# edition_3-1.net
KiCad netlist of a schematic drawn in EAGLE
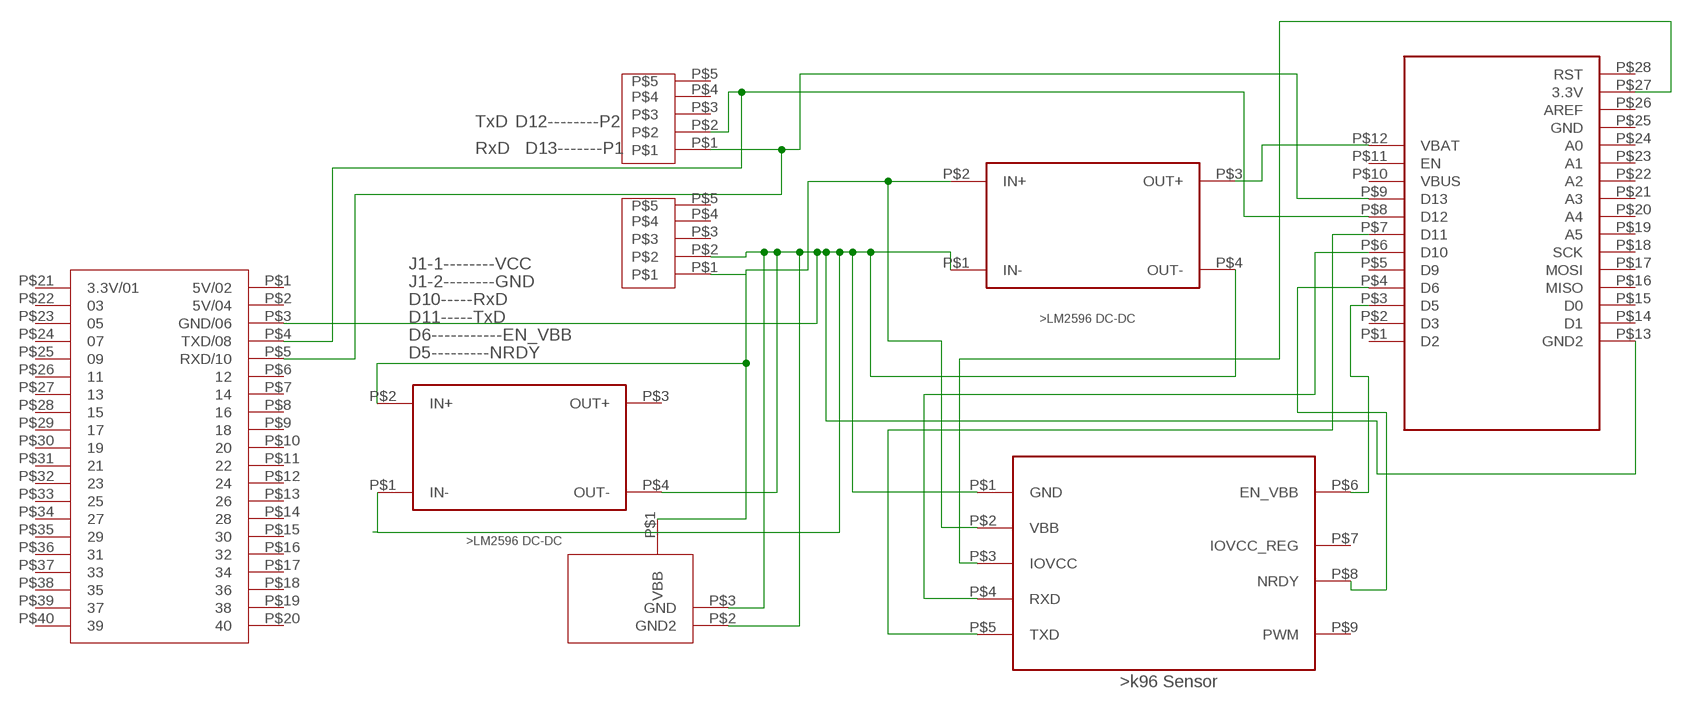
[diagram p0: schematic, sheet 1]

(export (version "E")
  (design (tool "Eeschema 10.0.6"))
  (components
    (comp (ref "DCDC1")
      (value "DCDC")
      (footprint "eagle-import:DCDC")
      (libsource (lib "eagle-import") (part "DCDC"))
    )
    (comp (ref "DCDC2")
      (value "DCDC")
      (footprint "eagle-import:DCDC")
      (libsource (lib "eagle-import") (part "DCDC"))
    )
    (comp (ref "FEATHER1")
      (value "FEATHER")
      (footprint "eagle-import:FEATHER")
      (libsource (lib "eagle-import") (part "FEATHER"))
    )
    (comp (ref "K96SENSOR1")
      (value "K96SENSOR")
      (footprint "eagle-import:K96SENSOR")
      (libsource (lib "eagle-import") (part "K96SENSOR"))
    )
    (comp (ref "PIN1")
      (value "PIN")
      (footprint "eagle-import:PIN")
      (libsource (lib "eagle-import") (part "PIN"))
    )
    (comp (ref "PIN2")
      (value "PIN")
      (footprint "eagle-import:PIN")
      (libsource (lib "eagle-import") (part "PIN"))
    )
    (comp (ref "U$1")
      (value "POWER")
      (footprint "eagle-import:POWERIN")
      (libsource (lib "eagle-import") (part "POWER"))
    )
    (comp (ref "U$2")
      (value "RASPBERRYPI")
      (footprint "eagle-import:RASPBERRYPI")
      (libsource (lib "eagle-import") (part "RASPBERRYPI"))
    )
  )
  (nets
    (net (code "1") (name "Net-(DCDC1-IN+)") (class "Default")
      (node (ref "DCDC1") (pin "P$2") (pinfunction "IN+_P$2") (pintype "bidirectional"))
      (node (ref "DCDC2") (pin "P$2") (pinfunction "IN+_P$2") (pintype "bidirectional"))
      (node (ref "K96SENSOR1") (pin "P$2") (pinfunction "VBB_P$2") (pintype "bidirectional"))
      (node (ref "PIN1") (pin "P$1") (pinfunction "P$1_P$1") (pintype "bidirectional"))
      (node (ref "U$1") (pin "P$1") (pinfunction "VBB_P$1") (pintype "bidirectional"))
    )
    (net (code "2") (name "Net-(DCDC1-IN-)") (class "Default")
      (node (ref "DCDC1") (pin "P$1") (pinfunction "IN-_P$1") (pintype "bidirectional"))
      (node (ref "DCDC1") (pin "P$4") (pinfunction "OUT-_P$4") (pintype "bidirectional"))
      (node (ref "DCDC2") (pin "P$1") (pinfunction "IN-_P$1") (pintype "bidirectional"))
      (node (ref "DCDC2") (pin "P$4") (pinfunction "OUT-_P$4") (pintype "bidirectional"))
      (node (ref "FEATHER1") (pin "P$13") (pinfunction "GND2_P$13") (pintype "bidirectional"))
      (node (ref "K96SENSOR1") (pin "P$1") (pinfunction "GND_P$1") (pintype "bidirectional"))
      (node (ref "PIN1") (pin "P$2") (pinfunction "P$2_P$2") (pintype "bidirectional"))
      (node (ref "U$1") (pin "P$2") (pinfunction "GND2_P$2") (pintype "bidirectional"))
      (node (ref "U$1") (pin "P$3") (pinfunction "GND_P$3") (pintype "bidirectional"))
      (node (ref "U$2") (pin "P$3") (pinfunction "GND/06_P$3") (pintype "bidirectional"))
    )
    (net (code "3") (name "Net-(DCDC1-OUT+)") (class "Default")
      (node (ref "DCDC1") (pin "P$3") (pinfunction "OUT+_P$3") (pintype "bidirectional"))
      (node (ref "FEATHER1") (pin "P$12") (pinfunction "VBAT_P$12") (pintype "bidirectional"))
    )
    (net (code "4") (name "Net-(FEATHER1-3.3V)") (class "Default")
      (node (ref "FEATHER1") (pin "P$27") (pinfunction "3.3V_P$27") (pintype "bidirectional"))
      (node (ref "K96SENSOR1") (pin "P$3") (pinfunction "IOVCC_P$3") (pintype "bidirectional"))
    )
    (net (code "5") (name "Net-(FEATHER1-D5)") (class "Default")
      (node (ref "FEATHER1") (pin "P$3") (pinfunction "D5_P$3") (pintype "bidirectional"))
      (node (ref "K96SENSOR1") (pin "P$6") (pinfunction "EN_VBB_P$6") (pintype "bidirectional"))
    )
    (net (code "6") (name "Net-(FEATHER1-D6)") (class "Default")
      (node (ref "FEATHER1") (pin "P$4") (pinfunction "D6_P$4") (pintype "bidirectional"))
      (node (ref "K96SENSOR1") (pin "P$8") (pinfunction "NRDY_P$8") (pintype "bidirectional"))
    )
    (net (code "7") (name "Net-(FEATHER1-D10)") (class "Default")
      (node (ref "FEATHER1") (pin "P$6") (pinfunction "D10_P$6") (pintype "bidirectional"))
      (node (ref "K96SENSOR1") (pin "P$4") (pinfunction "RXD_P$4") (pintype "bidirectional"))
    )
    (net (code "8") (name "Net-(FEATHER1-D11)") (class "Default")
      (node (ref "FEATHER1") (pin "P$7") (pinfunction "D11_P$7") (pintype "bidirectional"))
      (node (ref "K96SENSOR1") (pin "P$5") (pinfunction "TXD_P$5") (pintype "bidirectional"))
    )
    (net (code "9") (name "Net-(FEATHER1-D12)") (class "Default")
      (node (ref "FEATHER1") (pin "P$8") (pinfunction "D12_P$8") (pintype "bidirectional"))
      (node (ref "PIN2") (pin "P$2") (pinfunction "P$2_P$2") (pintype "bidirectional"))
      (node (ref "U$2") (pin "P$4") (pinfunction "TXD/08_P$4") (pintype "bidirectional"))
    )
    (net (code "10") (name "Net-(FEATHER1-D13)") (class "Default")
      (node (ref "FEATHER1") (pin "P$9") (pinfunction "D13_P$9") (pintype "bidirectional"))
      (node (ref "PIN2") (pin "P$1") (pinfunction "P$1_P$1") (pintype "bidirectional"))
      (node (ref "U$2") (pin "P$5") (pinfunction "RXD/10_P$5") (pintype "bidirectional"))
    )
    (net (code "11") (name "unconnected-(DCDC2-OUT+-PadP$3)") (class "Default")
      (node (ref "DCDC2") (pin "P$3") (pinfunction "OUT+_P$3") (pintype "bidirectional"))
    )
    (net (code "12") (name "unconnected-(FEATHER1-A0-PadP$24)") (class "Default")
      (node (ref "FEATHER1") (pin "P$24") (pinfunction "A0_P$24") (pintype "bidirectional"))
    )
    (net (code "13") (name "unconnected-(FEATHER1-A1-PadP$23)") (class "Default")
      (node (ref "FEATHER1") (pin "P$23") (pinfunction "A1_P$23") (pintype "bidirectional"))
    )
    (net (code "14") (name "unconnected-(FEATHER1-A2-PadP$22)") (class "Default")
      (node (ref "FEATHER1") (pin "P$22") (pinfunction "A2_P$22") (pintype "bidirectional"))
    )
    (net (code "15") (name "unconnected-(FEATHER1-A3-PadP$21)") (class "Default")
      (node (ref "FEATHER1") (pin "P$21") (pinfunction "A3_P$21") (pintype "bidirectional"))
    )
    (net (code "16") (name "unconnected-(FEATHER1-A4-PadP$20)") (class "Default")
      (node (ref "FEATHER1") (pin "P$20") (pinfunction "A4_P$20") (pintype "bidirectional"))
    )
    (net (code "17") (name "unconnected-(FEATHER1-A5-PadP$19)") (class "Default")
      (node (ref "FEATHER1") (pin "P$19") (pinfunction "A5_P$19") (pintype "bidirectional"))
    )
    (net (code "18") (name "unconnected-(FEATHER1-AREF-PadP$26)") (class "Default")
      (node (ref "FEATHER1") (pin "P$26") (pinfunction "AREF_P$26") (pintype "bidirectional"))
    )
    (net (code "19") (name "unconnected-(FEATHER1-D0-PadP$15)") (class "Default")
      (node (ref "FEATHER1") (pin "P$15") (pinfunction "D0_P$15") (pintype "bidirectional"))
    )
    (net (code "20") (name "unconnected-(FEATHER1-D1-PadP$14)") (class "Default")
      (node (ref "FEATHER1") (pin "P$14") (pinfunction "D1_P$14") (pintype "bidirectional"))
    )
    (net (code "21") (name "unconnected-(FEATHER1-D2-PadP$1)") (class "Default")
      (node (ref "FEATHER1") (pin "P$1") (pinfunction "D2_P$1") (pintype "bidirectional"))
    )
    (net (code "22") (name "unconnected-(FEATHER1-D3-PadP$2)") (class "Default")
      (node (ref "FEATHER1") (pin "P$2") (pinfunction "D3_P$2") (pintype "bidirectional"))
    )
    (net (code "23") (name "unconnected-(FEATHER1-D9-PadP$5)") (class "Default")
      (node (ref "FEATHER1") (pin "P$5") (pinfunction "D9_P$5") (pintype "bidirectional"))
    )
    (net (code "24") (name "unconnected-(FEATHER1-EN-PadP$11)") (class "Default")
      (node (ref "FEATHER1") (pin "P$11") (pinfunction "EN_P$11") (pintype "bidirectional"))
    )
    (net (code "25") (name "unconnected-(FEATHER1-GND-PadP$25)") (class "Default")
      (node (ref "FEATHER1") (pin "P$25") (pinfunction "GND_P$25") (pintype "bidirectional"))
    )
    (net (code "26") (name "unconnected-(FEATHER1-MISO-PadP$16)") (class "Default")
      (node (ref "FEATHER1") (pin "P$16") (pinfunction "MISO_P$16") (pintype "bidirectional"))
    )
    (net (code "27") (name "unconnected-(FEATHER1-MOSI-PadP$17)") (class "Default")
      (node (ref "FEATHER1") (pin "P$17") (pinfunction "MOSI_P$17") (pintype "bidirectional"))
    )
    (net (code "28") (name "unconnected-(FEATHER1-RST-PadP$28)") (class "Default")
      (node (ref "FEATHER1") (pin "P$28") (pinfunction "RST_P$28") (pintype "bidirectional"))
    )
    (net (code "29") (name "unconnected-(FEATHER1-SCK-PadP$18)") (class "Default")
      (node (ref "FEATHER1") (pin "P$18") (pinfunction "SCK_P$18") (pintype "bidirectional"))
    )
    (net (code "30") (name "unconnected-(FEATHER1-VBUS-PadP$10)") (class "Default")
      (node (ref "FEATHER1") (pin "P$10") (pinfunction "VBUS_P$10") (pintype "bidirectional"))
    )
    (net (code "31") (name "unconnected-(K96SENSOR1-IOVCC_REG-PadP$7)") (class "Default")
      (node (ref "K96SENSOR1") (pin "P$7") (pinfunction "IOVCC_REG_P$7") (pintype "bidirectional"))
    )
    (net (code "32") (name "unconnected-(K96SENSOR1-PWM-PadP$9)") (class "Default")
      (node (ref "K96SENSOR1") (pin "P$9") (pinfunction "PWM_P$9") (pintype "bidirectional"))
    )
    (net (code "33") (name "unconnected-(PIN1-PadP$3)") (class "Default")
      (node (ref "PIN1") (pin "P$3") (pinfunction "P$3_P$3") (pintype "bidirectional"))
    )
    (net (code "34") (name "unconnected-(PIN1-PadP$4)") (class "Default")
      (node (ref "PIN1") (pin "P$4") (pinfunction "P$4_P$4") (pintype "bidirectional"))
    )
    (net (code "35") (name "unconnected-(PIN1-PadP$5)") (class "Default")
      (node (ref "PIN1") (pin "P$5") (pinfunction "P$5_P$5") (pintype "bidirectional"))
    )
    (net (code "36") (name "unconnected-(PIN2-PadP$3)") (class "Default")
      (node (ref "PIN2") (pin "P$3") (pinfunction "P$3_P$3") (pintype "bidirectional"))
    )
    (net (code "37") (name "unconnected-(PIN2-PadP$4)") (class "Default")
      (node (ref "PIN2") (pin "P$4") (pinfunction "P$4_P$4") (pintype "bidirectional"))
    )
    (net (code "38") (name "unconnected-(PIN2-PadP$5)") (class "Default")
      (node (ref "PIN2") (pin "P$5") (pinfunction "P$5_P$5") (pintype "bidirectional"))
    )
    (net (code "39") (name "unconnected-(U$2-03-PadP$22)") (class "Default")
      (node (ref "U$2") (pin "P$22") (pinfunction "03_P$22") (pintype "bidirectional"))
    )
    (net (code "40") (name "unconnected-(U$2-3.3V{slash}01-PadP$21)") (class "Default")
      (node (ref "U$2") (pin "P$21") (pinfunction "3.3V/01_P$21") (pintype "bidirectional"))
    )
    (net (code "41") (name "unconnected-(U$2-05-PadP$23)") (class "Default")
      (node (ref "U$2") (pin "P$23") (pinfunction "05_P$23") (pintype "bidirectional"))
    )
    (net (code "42") (name "unconnected-(U$2-5V{slash}02-PadP$1)") (class "Default")
      (node (ref "U$2") (pin "P$1") (pinfunction "5V/02_P$1") (pintype "bidirectional"))
    )
    (net (code "43") (name "unconnected-(U$2-5V{slash}04-PadP$2)") (class "Default")
      (node (ref "U$2") (pin "P$2") (pinfunction "5V/04_P$2") (pintype "bidirectional"))
    )
    (net (code "44") (name "unconnected-(U$2-07-PadP$24)") (class "Default")
      (node (ref "U$2") (pin "P$24") (pinfunction "07_P$24") (pintype "bidirectional"))
    )
    (net (code "45") (name "unconnected-(U$2-09-PadP$25)") (class "Default")
      (node (ref "U$2") (pin "P$25") (pinfunction "09_P$25") (pintype "bidirectional"))
    )
    (net (code "46") (name "unconnected-(U$2-11-PadP$26)") (class "Default")
      (node (ref "U$2") (pin "P$26") (pinfunction "11_P$26") (pintype "bidirectional"))
    )
    (net (code "47") (name "unconnected-(U$2-12-PadP$6)") (class "Default")
      (node (ref "U$2") (pin "P$6") (pinfunction "12_P$6") (pintype "bidirectional"))
    )
    (net (code "48") (name "unconnected-(U$2-13-PadP$27)") (class "Default")
      (node (ref "U$2") (pin "P$27") (pinfunction "13_P$27") (pintype "bidirectional"))
    )
    (net (code "49") (name "unconnected-(U$2-14-PadP$7)") (class "Default")
      (node (ref "U$2") (pin "P$7") (pinfunction "14_P$7") (pintype "bidirectional"))
    )
    (net (code "50") (name "unconnected-(U$2-15-PadP$28)") (class "Default")
      (node (ref "U$2") (pin "P$28") (pinfunction "15_P$28") (pintype "bidirectional"))
    )
    (net (code "51") (name "unconnected-(U$2-16-PadP$8)") (class "Default")
      (node (ref "U$2") (pin "P$8") (pinfunction "16_P$8") (pintype "bidirectional"))
    )
    (net (code "52") (name "unconnected-(U$2-17-PadP$29)") (class "Default")
      (node (ref "U$2") (pin "P$29") (pinfunction "17_P$29") (pintype "bidirectional"))
    )
    (net (code "53") (name "unconnected-(U$2-18-PadP$9)") (class "Default")
      (node (ref "U$2") (pin "P$9") (pinfunction "18_P$9") (pintype "bidirectional"))
    )
    (net (code "54") (name "unconnected-(U$2-19-PadP$30)") (class "Default")
      (node (ref "U$2") (pin "P$30") (pinfunction "19_P$30") (pintype "bidirectional"))
    )
    (net (code "55") (name "unconnected-(U$2-20-PadP$10)") (class "Default")
      (node (ref "U$2") (pin "P$10") (pinfunction "20_P$10") (pintype "bidirectional"))
    )
    (net (code "56") (name "unconnected-(U$2-21-PadP$31)") (class "Default")
      (node (ref "U$2") (pin "P$31") (pinfunction "21_P$31") (pintype "bidirectional"))
    )
    (net (code "57") (name "unconnected-(U$2-22-PadP$11)") (class "Default")
      (node (ref "U$2") (pin "P$11") (pinfunction "22_P$11") (pintype "bidirectional"))
    )
    (net (code "58") (name "unconnected-(U$2-23-PadP$32)") (class "Default")
      (node (ref "U$2") (pin "P$32") (pinfunction "23_P$32") (pintype "bidirectional"))
    )
    (net (code "59") (name "unconnected-(U$2-24-PadP$12)") (class "Default")
      (node (ref "U$2") (pin "P$12") (pinfunction "24_P$12") (pintype "bidirectional"))
    )
    (net (code "60") (name "unconnected-(U$2-25-PadP$33)") (class "Default")
      (node (ref "U$2") (pin "P$33") (pinfunction "25_P$33") (pintype "bidirectional"))
    )
    (net (code "61") (name "unconnected-(U$2-26-PadP$13)") (class "Default")
      (node (ref "U$2") (pin "P$13") (pinfunction "26_P$13") (pintype "bidirectional"))
    )
    (net (code "62") (name "unconnected-(U$2-27-PadP$34)") (class "Default")
      (node (ref "U$2") (pin "P$34") (pinfunction "27_P$34") (pintype "bidirectional"))
    )
    (net (code "63") (name "unconnected-(U$2-28-PadP$14)") (class "Default")
      (node (ref "U$2") (pin "P$14") (pinfunction "28_P$14") (pintype "bidirectional"))
    )
    (net (code "64") (name "unconnected-(U$2-29-PadP$35)") (class "Default")
      (node (ref "U$2") (pin "P$35") (pinfunction "29_P$35") (pintype "bidirectional"))
    )
    (net (code "65") (name "unconnected-(U$2-30-PadP$15)") (class "Default")
      (node (ref "U$2") (pin "P$15") (pinfunction "30_P$15") (pintype "bidirectional"))
    )
    (net (code "66") (name "unconnected-(U$2-31-PadP$36)") (class "Default")
      (node (ref "U$2") (pin "P$36") (pinfunction "31_P$36") (pintype "bidirectional"))
    )
    (net (code "67") (name "unconnected-(U$2-32-PadP$16)") (class "Default")
      (node (ref "U$2") (pin "P$16") (pinfunction "32_P$16") (pintype "bidirectional"))
    )
    (net (code "68") (name "unconnected-(U$2-33-PadP$37)") (class "Default")
      (node (ref "U$2") (pin "P$37") (pinfunction "33_P$37") (pintype "bidirectional"))
    )
    (net (code "69") (name "unconnected-(U$2-34-PadP$17)") (class "Default")
      (node (ref "U$2") (pin "P$17") (pinfunction "34_P$17") (pintype "bidirectional"))
    )
    (net (code "70") (name "unconnected-(U$2-35-PadP$38)") (class "Default")
      (node (ref "U$2") (pin "P$38") (pinfunction "35_P$38") (pintype "bidirectional"))
    )
    (net (code "71") (name "unconnected-(U$2-36-PadP$18)") (class "Default")
      (node (ref "U$2") (pin "P$18") (pinfunction "36_P$18") (pintype "bidirectional"))
    )
    (net (code "72") (name "unconnected-(U$2-37-PadP$39)") (class "Default")
      (node (ref "U$2") (pin "P$39") (pinfunction "37_P$39") (pintype "bidirectional"))
    )
    (net (code "73") (name "unconnected-(U$2-38-PadP$19)") (class "Default")
      (node (ref "U$2") (pin "P$19") (pinfunction "38_P$19") (pintype "bidirectional"))
    )
    (net (code "74") (name "unconnected-(U$2-39-PadP$40)") (class "Default")
      (node (ref "U$2") (pin "P$40") (pinfunction "39_P$40") (pintype "bidirectional"))
    )
    (net (code "75") (name "unconnected-(U$2-40-PadP$20)") (class "Default")
      (node (ref "U$2") (pin "P$20") (pinfunction "40_P$20") (pintype "bidirectional"))
    )
  )
)
